# Power_Supply_Section.net
KiCad netlist of a schematic drawn in Altium Designer
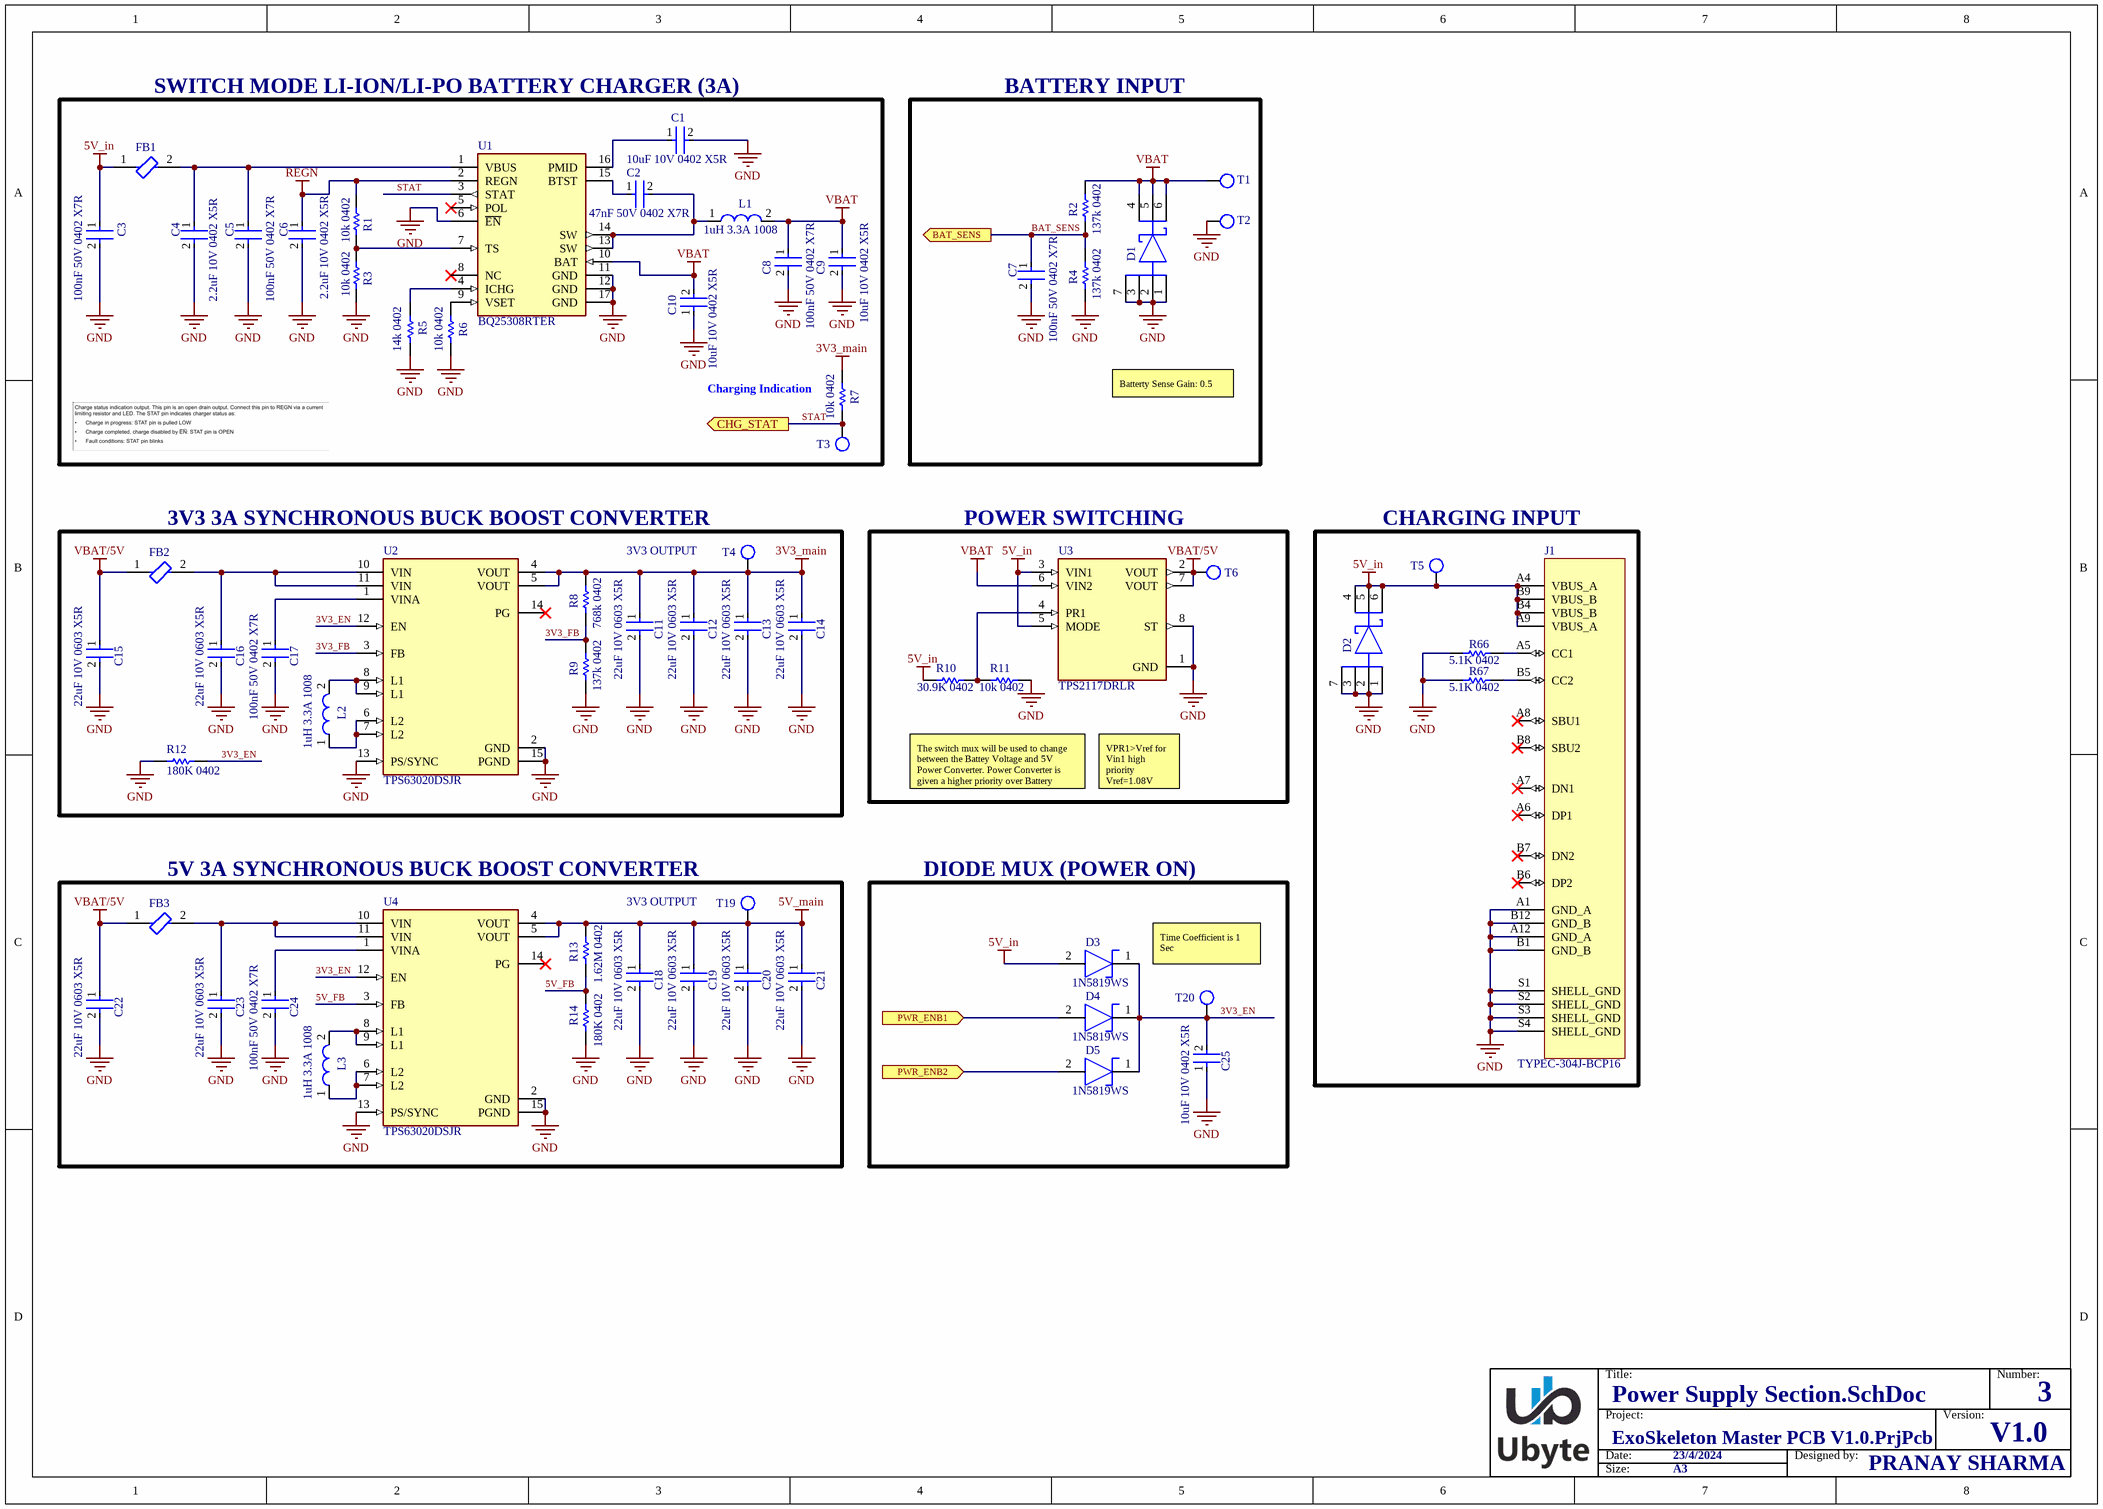
[diagram p0: Power Supply Section.SchDoc]

(export (version "E")
  (design (tool "Eeschema 10.0.6"))
  (components
    (comp (ref "C1")
      (value "10uF 10V 0402 X5R")
      (footprint "Res, Cap, Ind, LED, FB_Lib:0402 IPC CLASS C CAPACITOR")
      (libsource (lib "Capacitor_Lib") (part "10uF 10V 0402 X5R"))
    )
    (comp (ref "C2")
      (value "47nF 50V 0402 X7R")
      (footprint "Res, Cap, Ind, LED, FB_Lib:0402 IPC CLASS C CAPACITOR")
      (libsource (lib "Capacitor_Lib") (part "47nF 50V 0402 X7R"))
    )
    (comp (ref "C3")
      (value "100nF 50V 0402 X7R")
      (footprint "Res, Cap, Ind, LED, FB_Lib:0402 IPC CLASS C CAPACITOR")
      (libsource (lib "Capacitor_Lib") (part "100nF 50V 0402 X7R"))
    )
    (comp (ref "C4")
      (value "2.2uF 10V 0402 X5R")
      (footprint "Res, Cap, Ind, LED, FB_Lib:0402 IPC CLASS C CAPACITOR")
      (libsource (lib "Capacitor_Lib") (part "2.2uF 10V 0402 X5R"))
    )
    (comp (ref "C5")
      (value "100nF 50V 0402 X7R")
      (footprint "Res, Cap, Ind, LED, FB_Lib:0402 IPC CLASS C CAPACITOR")
      (libsource (lib "Capacitor_Lib") (part "100nF 50V 0402 X7R"))
    )
    (comp (ref "C6")
      (value "2.2uF 10V 0402 X5R")
      (footprint "Res, Cap, Ind, LED, FB_Lib:0402 IPC CLASS C CAPACITOR")
      (libsource (lib "Capacitor_Lib") (part "2.2uF 10V 0402 X5R"))
    )
    (comp (ref "C7")
      (value "100nF 50V 0402 X7R")
      (footprint "Res, Cap, Ind, LED, FB_Lib:0402 IPC CLASS C CAPACITOR")
      (libsource (lib "Capacitor_Lib") (part "100nF 50V 0402 X7R"))
    )
    (comp (ref "C8")
      (value "100nF 50V 0402 X7R")
      (footprint "Res, Cap, Ind, LED, FB_Lib:0402 IPC CLASS C CAPACITOR")
      (libsource (lib "Capacitor_Lib") (part "100nF 50V 0402 X7R"))
    )
    (comp (ref "C9")
      (value "10uF 10V 0402 X5R")
      (footprint "Res, Cap, Ind, LED, FB_Lib:0402 IPC CLASS C CAPACITOR")
      (libsource (lib "Capacitor_Lib") (part "10uF 10V 0402 X5R"))
    )
    (comp (ref "C10")
      (value "10uF 10V 0402 X5R")
      (footprint "Res, Cap, Ind, LED, FB_Lib:0402 IPC CLASS C CAPACITOR")
      (libsource (lib "Capacitor_Lib") (part "10uF 10V 0402 X5R"))
    )
    (comp (ref "C11")
      (value "22uF 10V 0603 X5R")
      (footprint "Res, Cap, Ind, LED, FB_Lib:0603 IPC CLASS C CAPACITOR")
      (libsource (lib "Capacitor_Lib") (part "22uF 10V 0603 X5R"))
    )
    (comp (ref "C12")
      (value "22uF 10V 0603 X5R")
      (footprint "Res, Cap, Ind, LED, FB_Lib:0603 IPC CLASS C CAPACITOR")
      (libsource (lib "Capacitor_Lib") (part "22uF 10V 0603 X5R"))
    )
    (comp (ref "C13")
      (value "22uF 10V 0603 X5R")
      (footprint "Res, Cap, Ind, LED, FB_Lib:0603 IPC CLASS C CAPACITOR")
      (libsource (lib "Capacitor_Lib") (part "22uF 10V 0603 X5R"))
    )
    (comp (ref "C14")
      (value "22uF 10V 0603 X5R")
      (footprint "Res, Cap, Ind, LED, FB_Lib:0603 IPC CLASS C CAPACITOR")
      (libsource (lib "Capacitor_Lib") (part "22uF 10V 0603 X5R"))
    )
    (comp (ref "C15")
      (value "22uF 10V 0603 X5R")
      (footprint "Res, Cap, Ind, LED, FB_Lib:0603 IPC CLASS C CAPACITOR")
      (libsource (lib "Capacitor_Lib") (part "22uF 10V 0603 X5R"))
    )
    (comp (ref "C16")
      (value "22uF 10V 0603 X5R")
      (footprint "Res, Cap, Ind, LED, FB_Lib:0603 IPC CLASS C CAPACITOR")
      (libsource (lib "Capacitor_Lib") (part "22uF 10V 0603 X5R"))
    )
    (comp (ref "C17")
      (value "100nF 50V 0402 X7R")
      (footprint "Res, Cap, Ind, LED, FB_Lib:0402 IPC CLASS C CAPACITOR")
      (libsource (lib "Capacitor_Lib") (part "100nF 50V 0402 X7R"))
    )
    (comp (ref "C18")
      (value "22uF 10V 0603 X5R")
      (footprint "Res, Cap, Ind, LED, FB_Lib:0603 IPC CLASS C CAPACITOR")
      (libsource (lib "Capacitor_Lib") (part "22uF 10V 0603 X5R"))
    )
    (comp (ref "C19")
      (value "22uF 10V 0603 X5R")
      (footprint "Res, Cap, Ind, LED, FB_Lib:0603 IPC CLASS C CAPACITOR")
      (libsource (lib "Capacitor_Lib") (part "22uF 10V 0603 X5R"))
    )
    (comp (ref "C20")
      (value "22uF 10V 0603 X5R")
      (footprint "Res, Cap, Ind, LED, FB_Lib:0603 IPC CLASS C CAPACITOR")
      (libsource (lib "Capacitor_Lib") (part "22uF 10V 0603 X5R"))
    )
    (comp (ref "C21")
      (value "22uF 10V 0603 X5R")
      (footprint "Res, Cap, Ind, LED, FB_Lib:0603 IPC CLASS C CAPACITOR")
      (libsource (lib "Capacitor_Lib") (part "22uF 10V 0603 X5R"))
    )
    (comp (ref "C22")
      (value "22uF 10V 0603 X5R")
      (footprint "Res, Cap, Ind, LED, FB_Lib:0603 IPC CLASS C CAPACITOR")
      (libsource (lib "Capacitor_Lib") (part "22uF 10V 0603 X5R"))
    )
    (comp (ref "C23")
      (value "22uF 10V 0603 X5R")
      (footprint "Res, Cap, Ind, LED, FB_Lib:0603 IPC CLASS C CAPACITOR")
      (libsource (lib "Capacitor_Lib") (part "22uF 10V 0603 X5R"))
    )
    (comp (ref "C24")
      (value "100nF 50V 0402 X7R")
      (footprint "Res, Cap, Ind, LED, FB_Lib:0402 IPC CLASS C CAPACITOR")
      (libsource (lib "Capacitor_Lib") (part "100nF 50V 0402 X7R"))
    )
    (comp (ref "C25")
      (value "10uF 10V 0402 X5R")
      (footprint "Res, Cap, Ind, LED, FB_Lib:0402 IPC CLASS C CAPACITOR")
      (libsource (lib "Capacitor_Lib") (part "10uF 10V 0402 X5R"))
    )
    (comp (ref "D1")
      (value "~")
      (footprint "Res, Cap, Ind, LED, FB_Lib:DRV0006A IPC-C")
      (libsource (lib "Diodes_Lib") (part "TVS0500DRVR"))
    )
    (comp (ref "D2")
      (value "~")
      (footprint "Res, Cap, Ind, LED, FB_Lib:DRV0006A IPC-C")
      (libsource (lib "Diodes_Lib") (part "TVS0500DRVR"))
    )
    (comp (ref "D3")
      (value "1N5819WS")
      (footprint "Res, Cap, Ind, LED, FB_Lib:SOD-323 IPC-C")
      (libsource (lib "Diodes_Lib") (part "1N5819WS"))
    )
    (comp (ref "D4")
      (value "1N5819WS")
      (footprint "Res, Cap, Ind, LED, FB_Lib:SOD-323 IPC-C")
      (libsource (lib "Diodes_Lib") (part "1N5819WS"))
    )
    (comp (ref "D5")
      (value "1N5819WS")
      (footprint "Res, Cap, Ind, LED, FB_Lib:SOD-323 IPC-C")
      (libsource (lib "Diodes_Lib") (part "1N5819WS"))
    )
    (comp (ref "FB1")
      (value "BLM21SP111SN1D")
      (footprint "Res, Cap, Ind, LED, FB_Lib:0603 IPC CLASS C FERRITE BEAD")
      (libsource (lib "Ferrite_Bead_Lib") (part "BLM21SP111SN1D"))
    )
    (comp (ref "FB2")
      (value "BLM21SP111SN1D")
      (footprint "Res, Cap, Ind, LED, FB_Lib:0603 IPC CLASS C FERRITE BEAD")
      (libsource (lib "Ferrite_Bead_Lib") (part "BLM21SP111SN1D"))
    )
    (comp (ref "FB3")
      (value "BLM21SP111SN1D")
      (footprint "Res, Cap, Ind, LED, FB_Lib:0603 IPC CLASS C FERRITE BEAD")
      (libsource (lib "Ferrite_Bead_Lib") (part "BLM21SP111SN1D"))
    )
    (comp (ref "J1")
      (value "TYPEC-304J-BCP16")
      (footprint "VALCON_CSP-USC16-TR")
      (libsource (lib "V1.0") (part "USB Type C"))
    )
    (comp (ref "L1")
      (value "1uH 3.3A 1008")
      (footprint "Res, Cap, Ind, LED, FB_Lib:1008 Inductor IPC-C")
      (libsource (lib "Inductor_Lib") (part "DFE252012F-1R0M=P2"))
    )
    (comp (ref "L2")
      (value "1uH 3.3A 1008")
      (footprint "Res, Cap, Ind, LED, FB_Lib:1008 Inductor IPC-C")
      (libsource (lib "Inductor_Lib") (part "DFE252012F-1R0M=P2"))
    )
    (comp (ref "L3")
      (value "1uH 3.3A 1008")
      (footprint "Res, Cap, Ind, LED, FB_Lib:1008 Inductor IPC-C")
      (libsource (lib "Inductor_Lib") (part "DFE252012F-1R0M=P2"))
    )
    (comp (ref "R1")
      (value "10k 0402")
      (footprint "Res, Cap, Ind, LED, FB_Lib:0402 IPC CLASS C RESISTOR")
      (libsource (lib "Resistor_Lib") (part "10k 1% 0402"))
    )
    (comp (ref "R2")
      (value "137k 0402")
      (footprint "Res, Cap, Ind, LED, FB_Lib:0402 IPC CLASS C RESISTOR")
      (libsource (lib "Resistor_Lib") (part "10k 1% 0402"))
    )
    (comp (ref "R3")
      (value "10k 0402")
      (footprint "Res, Cap, Ind, LED, FB_Lib:0402 IPC CLASS C RESISTOR")
      (libsource (lib "Resistor_Lib") (part "10k 1% 0402"))
    )
    (comp (ref "R4")
      (value "137k 0402")
      (footprint "Res, Cap, Ind, LED, FB_Lib:0402 IPC CLASS C RESISTOR")
      (libsource (lib "Resistor_Lib") (part "10k 1% 0402"))
    )
    (comp (ref "R5")
      (value "14k 0402")
      (footprint "Res, Cap, Ind, LED, FB_Lib:0402 IPC CLASS C RESISTOR")
      (libsource (lib "Resistor_Lib") (part "14k 1% 0402"))
    )
    (comp (ref "R6")
      (value "10k 0402")
      (footprint "Res, Cap, Ind, LED, FB_Lib:0402 IPC CLASS C RESISTOR")
      (libsource (lib "Resistor_Lib") (part "10k 1% 0402"))
    )
    (comp (ref "R7")
      (value "10k 0402")
      (footprint "Res, Cap, Ind, LED, FB_Lib:0402 IPC CLASS C RESISTOR")
      (libsource (lib "Resistor_Lib") (part "10k 1% 0402"))
    )
    (comp (ref "R8")
      (value "768k 0402")
      (footprint "Res, Cap, Ind, LED, FB_Lib:0402 IPC CLASS C RESISTOR")
      (libsource (lib "Resistor_Lib") (part "10k 1% 0402"))
    )
    (comp (ref "R9")
      (value "137k 0402")
      (footprint "Res, Cap, Ind, LED, FB_Lib:0402 IPC CLASS C RESISTOR")
      (libsource (lib "Resistor_Lib") (part "10k 1% 0402"))
    )
    (comp (ref "R10")
      (value "30.9K 0402")
      (footprint "Res, Cap, Ind, LED, FB_Lib:0402 IPC CLASS C RESISTOR")
      (libsource (lib "Resistor_Lib") (part "30.9K 1%  0402"))
    )
    (comp (ref "R11")
      (value "10k 0402")
      (footprint "Res, Cap, Ind, LED, FB_Lib:0402 IPC CLASS C RESISTOR")
      (libsource (lib "Resistor_Lib") (part "10k 1% 0402"))
    )
    (comp (ref "R12")
      (value "180K 0402")
      (footprint "Res, Cap, Ind, LED, FB_Lib:0402 IPC CLASS C RESISTOR")
      (libsource (lib "Resistor_Lib") (part "180K 1% 0402"))
    )
    (comp (ref "R13")
      (value "1.62M 0402")
      (footprint "Res, Cap, Ind, LED, FB_Lib:0402 IPC CLASS C RESISTOR")
      (libsource (lib "Resistor_Lib") (part "1.62M 1% 0402"))
    )
    (comp (ref "R14")
      (value "180K 0402")
      (footprint "Res, Cap, Ind, LED, FB_Lib:0402 IPC CLASS C RESISTOR")
      (libsource (lib "Resistor_Lib") (part "180K 1% 0402"))
    )
    (comp (ref "R66")
      (value "5.1K 0402")
      (footprint "Res, Cap, Ind, LED, FB_Lib:0402 IPC CLASS C RESISTOR")
      (libsource (lib "Resistor_Lib") (part "5.1K 1% 0402"))
    )
    (comp (ref "R67")
      (value "5.1K 0402")
      (footprint "Res, Cap, Ind, LED, FB_Lib:0402 IPC CLASS C RESISTOR")
      (libsource (lib "Resistor_Lib") (part "5.1K 1% 0402"))
    )
    (comp (ref "T1")
      (value "Test Point TH")
      (footprint "Miscellaneous_Lib:Test Point TH")
      (libsource (lib "Miscellaneous_Lib") (part "Test Point TH"))
    )
    (comp (ref "T2")
      (value "Test Point TH")
      (footprint "Miscellaneous_Lib:Test Point TH")
      (libsource (lib "Miscellaneous_Lib") (part "Test Point TH"))
    )
    (comp (ref "T3")
      (value "TP")
      (footprint "Miscellaneous_Lib:Testpoint1")
      (libsource (lib "Miscellaneous_Lib") (part "Testpoint1"))
    )
    (comp (ref "T4")
      (value "TP")
      (footprint "Miscellaneous_Lib:Testpoint1")
      (libsource (lib "Miscellaneous_Lib") (part "Testpoint1"))
    )
    (comp (ref "T5")
      (value "TP")
      (footprint "Miscellaneous_Lib:Testpoint1")
      (libsource (lib "Miscellaneous_Lib") (part "Testpoint1"))
    )
    (comp (ref "T6")
      (value "TP")
      (footprint "Miscellaneous_Lib:Testpoint1")
      (libsource (lib "Miscellaneous_Lib") (part "Testpoint1"))
    )
    (comp (ref "T19")
      (value "TP")
      (footprint "Miscellaneous_Lib:Testpoint1")
      (libsource (lib "Miscellaneous_Lib") (part "Testpoint1"))
    )
    (comp (ref "T20")
      (value "TP")
      (footprint "Miscellaneous_Lib:Testpoint1")
      (libsource (lib "Miscellaneous_Lib") (part "Testpoint1"))
    )
    (comp (ref "U1")
      (value "BQ25308RTER")
      (footprint "Integrated_Circuits_Lib:RTE0016C IPC-C")
      (libsource (lib "Integrated_Circuits_Lib") (part "BQ25308RTER"))
    )
    (comp (ref "U2")
      (value "TPS63020DSJR")
      (footprint "FP-DSJ0014A-MFG")
      (libsource (lib "Altium Content Vault") (part "ca84f4b88d1e031d86a58c77b9c066d"))
    )
    (comp (ref "U3")
      (value "TPS2117DRLR")
      (footprint "Integrated_Circuits_Lib:DRL0008A IPC-C")
      (libsource (lib "Integrated_Circuits_Lib") (part "TPS2117DRLR"))
    )
    (comp (ref "U4")
      (value "TPS63020DSJR")
      (footprint "FP-DSJ0014A-MFG")
      (libsource (lib "Altium Content Vault") (part "ca84f4b88d1e031d86a58c77b9c066d"))
    )
  )
  (nets
    (net (code "1") (name "/3V3_EN") (class "Default")
      (node (ref "C25") (pin "2") (pinfunction "2_2") (pintype "passive"))
      (node (ref "D3") (pin "1") (pinfunction "C_1") (pintype "passive"))
      (node (ref "D4") (pin "1") (pinfunction "C_1") (pintype "passive"))
      (node (ref "D5") (pin "1") (pinfunction "C_1") (pintype "passive"))
      (node (ref "R12") (pin "1") (pinfunction "1_1") (pintype "passive"))
      (node (ref "T20") (pin "0") (pinfunction "0_0") (pintype "passive"))
      (node (ref "U2") (pin "12") (pinfunction "EN_12") (pintype "input"))
      (node (ref "U4") (pin "12") (pinfunction "EN_12") (pintype "input"))
    )
    (net (code "2") (name "/3V3_FB") (class "Default")
      (node (ref "R8") (pin "2") (pinfunction "2_2") (pintype "passive"))
      (node (ref "R9") (pin "2") (pinfunction "2_2") (pintype "passive"))
      (node (ref "U2") (pin "3") (pinfunction "FB_3") (pintype "input"))
    )
    (net (code "3") (name "/5V_FB") (class "Default")
      (node (ref "R13") (pin "1") (pinfunction "1_1") (pintype "passive"))
      (node (ref "R14") (pin "2") (pinfunction "2_2") (pintype "passive"))
      (node (ref "U4") (pin "3") (pinfunction "FB_3") (pintype "input"))
    )
    (net (code "4") (name "/BAT_SENS") (class "Default")
      (node (ref "C7") (pin "1") (pinfunction "1_1") (pintype "passive"))
      (node (ref "R2") (pin "1") (pinfunction "1_1") (pintype "passive"))
      (node (ref "R4") (pin "2") (pinfunction "2_2") (pintype "passive"))
    )
    (net (code "5") (name "/PWR_ENB1") (class "Default")
      (node (ref "D4") (pin "2") (pinfunction "A_2") (pintype "passive"))
    )
    (net (code "6") (name "/PWR_ENB2") (class "Default")
      (node (ref "D5") (pin "2") (pinfunction "A_2") (pintype "passive"))
    )
    (net (code "7") (name "/STAT") (class "Default")
      (node (ref "R7") (pin "1") (pinfunction "1_1") (pintype "passive"))
      (node (ref "T3") (pin "0") (pinfunction "0_0") (pintype "passive"))
      (node (ref "U1") (pin "3") (pinfunction "STAT_3") (pintype "output"))
    )
    (net (code "8") (name "3V3_main") (class "Default")
      (node (ref "C11") (pin "1") (pinfunction "1_1") (pintype "passive"))
      (node (ref "C12") (pin "1") (pinfunction "1_1") (pintype "passive"))
      (node (ref "C13") (pin "1") (pinfunction "1_1") (pintype "passive"))
      (node (ref "C14") (pin "1") (pinfunction "1_1") (pintype "passive"))
      (node (ref "R7") (pin "2") (pinfunction "2_2") (pintype "passive"))
      (node (ref "R8") (pin "1") (pinfunction "1_1") (pintype "passive"))
      (node (ref "T4") (pin "0") (pinfunction "0_0") (pintype "passive"))
      (node (ref "U2") (pin "4") (pinfunction "VOUT_4") (pintype "power_in"))
      (node (ref "U2") (pin "5") (pinfunction "VOUT_5") (pintype "power_in"))
    )
    (net (code "9") (name "5V_in") (class "Default")
      (node (ref "C3") (pin "1") (pinfunction "1_1") (pintype "passive"))
      (node (ref "D2") (pin "4") (pinfunction "4_4") (pintype "passive"))
      (node (ref "D2") (pin "5") (pinfunction "5_5") (pintype "passive"))
      (node (ref "D2") (pin "6") (pinfunction "6_6") (pintype "passive"))
      (node (ref "D3") (pin "2") (pinfunction "A_2") (pintype "passive"))
      (node (ref "FB1") (pin "1") (pinfunction "1_1") (pintype "passive"))
      (node (ref "J1") (pin "A4") (pinfunction "VBUS_A_A4") (pintype "power_in"))
      (node (ref "J1") (pin "A9") (pinfunction "VBUS_A_A9") (pintype "power_in"))
      (node (ref "J1") (pin "B4") (pinfunction "VBUS_B_B4") (pintype "power_in"))
      (node (ref "J1") (pin "B9") (pinfunction "VBUS_B_B9") (pintype "power_in"))
      (node (ref "R10") (pin "2") (pinfunction "2_2") (pintype "passive"))
      (node (ref "T5") (pin "0") (pinfunction "0_0") (pintype "passive"))
      (node (ref "U3") (pin "3") (pinfunction "VIN1_3") (pintype "input"))
      (node (ref "U3") (pin "5") (pinfunction "MODE_5") (pintype "input"))
    )
    (net (code "10") (name "5V_main") (class "Default")
      (node (ref "C18") (pin "1") (pinfunction "1_1") (pintype "passive"))
      (node (ref "C19") (pin "1") (pinfunction "1_1") (pintype "passive"))
      (node (ref "C20") (pin "1") (pinfunction "1_1") (pintype "passive"))
      (node (ref "C21") (pin "1") (pinfunction "1_1") (pintype "passive"))
      (node (ref "R13") (pin "2") (pinfunction "2_2") (pintype "passive"))
      (node (ref "T19") (pin "0") (pinfunction "0_0") (pintype "passive"))
      (node (ref "U4") (pin "4") (pinfunction "VOUT_4") (pintype "power_in"))
      (node (ref "U4") (pin "5") (pinfunction "VOUT_5") (pintype "power_in"))
    )
    (net (code "11") (name "GND") (class "Default")
      (node (ref "C1") (pin "2") (pinfunction "2_2") (pintype "passive"))
      (node (ref "C10") (pin "1") (pinfunction "1_1") (pintype "passive"))
      (node (ref "C11") (pin "2") (pinfunction "2_2") (pintype "passive"))
      (node (ref "C12") (pin "2") (pinfunction "2_2") (pintype "passive"))
      (node (ref "C13") (pin "2") (pinfunction "2_2") (pintype "passive"))
      (node (ref "C14") (pin "2") (pinfunction "2_2") (pintype "passive"))
      (node (ref "C15") (pin "2") (pinfunction "2_2") (pintype "passive"))
      (node (ref "C16") (pin "2") (pinfunction "2_2") (pintype "passive"))
      (node (ref "C17") (pin "2") (pinfunction "2_2") (pintype "passive"))
      (node (ref "C18") (pin "2") (pinfunction "2_2") (pintype "passive"))
      (node (ref "C19") (pin "2") (pinfunction "2_2") (pintype "passive"))
      (node (ref "C20") (pin "2") (pinfunction "2_2") (pintype "passive"))
      (node (ref "C21") (pin "2") (pinfunction "2_2") (pintype "passive"))
      (node (ref "C22") (pin "2") (pinfunction "2_2") (pintype "passive"))
      (node (ref "C23") (pin "2") (pinfunction "2_2") (pintype "passive"))
      (node (ref "C24") (pin "2") (pinfunction "2_2") (pintype "passive"))
      (node (ref "C25") (pin "1") (pinfunction "1_1") (pintype "passive"))
      (node (ref "C3") (pin "2") (pinfunction "2_2") (pintype "passive"))
      (node (ref "C4") (pin "2") (pinfunction "2_2") (pintype "passive"))
      (node (ref "C5") (pin "2") (pinfunction "2_2") (pintype "passive"))
      (node (ref "C6") (pin "2") (pinfunction "2_2") (pintype "passive"))
      (node (ref "C7") (pin "2") (pinfunction "2_2") (pintype "passive"))
      (node (ref "C8") (pin "2") (pinfunction "2_2") (pintype "passive"))
      (node (ref "C9") (pin "2") (pinfunction "2_2") (pintype "passive"))
      (node (ref "D1") (pin "1") (pinfunction "C_1") (pintype "passive"))
      (node (ref "D1") (pin "2") (pinfunction "A_2") (pintype "passive"))
      (node (ref "D1") (pin "3") (pinfunction "3_3") (pintype "passive"))
      (node (ref "D1") (pin "7") (pinfunction "7_7") (pintype "passive"))
      (node (ref "D2") (pin "1") (pinfunction "C_1") (pintype "passive"))
      (node (ref "D2") (pin "2") (pinfunction "A_2") (pintype "passive"))
      (node (ref "D2") (pin "3") (pinfunction "3_3") (pintype "passive"))
      (node (ref "D2") (pin "7") (pinfunction "7_7") (pintype "passive"))
      (node (ref "J1") (pin "A1") (pinfunction "GND_A_A1") (pintype "power_in"))
      (node (ref "J1") (pin "A12") (pinfunction "GND_A_A12") (pintype "power_in"))
      (node (ref "J1") (pin "B1") (pinfunction "GND_B_B1") (pintype "power_in"))
      (node (ref "J1") (pin "B12") (pinfunction "GND_B_B12") (pintype "power_in"))
      (node (ref "J1") (pin "S1") (pinfunction "SHELL_GND_S1") (pintype "power_in"))
      (node (ref "J1") (pin "S2") (pinfunction "SHELL_GND_S2") (pintype "power_in"))
      (node (ref "J1") (pin "S3") (pinfunction "SHELL_GND_S3") (pintype "power_in"))
      (node (ref "J1") (pin "S4") (pinfunction "SHELL_GND_S4") (pintype "power_in"))
      (node (ref "R11") (pin "1") (pinfunction "1_1") (pintype "passive"))
      (node (ref "R12") (pin "2") (pinfunction "2_2") (pintype "passive"))
      (node (ref "R14") (pin "1") (pinfunction "1_1") (pintype "passive"))
      (node (ref "R3") (pin "1") (pinfunction "1_1") (pintype "passive"))
      (node (ref "R4") (pin "1") (pinfunction "1_1") (pintype "passive"))
      (node (ref "R5") (pin "1") (pinfunction "1_1") (pintype "passive"))
      (node (ref "R6") (pin "1") (pinfunction "1_1") (pintype "passive"))
      (node (ref "R66") (pin "1") (pinfunction "1_1") (pintype "passive"))
      (node (ref "R67") (pin "1") (pinfunction "1_1") (pintype "passive"))
      (node (ref "R9") (pin "1") (pinfunction "1_1") (pintype "passive"))
      (node (ref "T2") (pin "0") (pinfunction "0_0") (pintype "passive"))
      (node (ref "U1") (pin "11") (pinfunction "GND_11") (pintype "power_in"))
      (node (ref "U1") (pin "12") (pinfunction "GND_12") (pintype "power_in"))
      (node (ref "U1") (pin "17") (pinfunction "GND_17") (pintype "power_in"))
      (node (ref "U1") (pin "6") (pinfunction "~{EN}_6") (pintype "passive"))
      (node (ref "U2") (pin "13") (pinfunction "PS/SYNC_13") (pintype "input"))
      (node (ref "U2") (pin "15") (pinfunction "PGND_15") (pintype "power_in"))
      (node (ref "U2") (pin "2") (pinfunction "GND_2") (pintype "power_in"))
      (node (ref "U3") (pin "1") (pinfunction "GND_1") (pintype "power_in"))
      (node (ref "U3") (pin "8") (pinfunction "ST_8") (pintype "output"))
      (node (ref "U4") (pin "13") (pinfunction "PS/SYNC_13") (pintype "input"))
      (node (ref "U4") (pin "15") (pinfunction "PGND_15") (pintype "power_in"))
      (node (ref "U4") (pin "2") (pinfunction "GND_2") (pintype "power_in"))
    )
    (net (code "12") (name "Net-(C2-Pad2)") (class "Default")
      (node (ref "C2") (pin "2") (pinfunction "2_2") (pintype "passive"))
      (node (ref "L1") (pin "1") (pinfunction "1_1") (pintype "passive"))
      (node (ref "U1") (pin "13") (pinfunction "SW_13") (pintype "output"))
      (node (ref "U1") (pin "14") (pinfunction "SW_14") (pintype "output"))
    )
    (net (code "13") (name "Net-(C16-Pad1)") (class "Default")
      (node (ref "C16") (pin "1") (pinfunction "1_1") (pintype "passive"))
      (node (ref "FB2") (pin "2") (pinfunction "2_2") (pintype "passive"))
      (node (ref "U2") (pin "10") (pinfunction "VIN_10") (pintype "power_in"))
      (node (ref "U2") (pin "11") (pinfunction "VIN_11") (pintype "power_in"))
    )
    (net (code "14") (name "Net-(C23-Pad1)") (class "Default")
      (node (ref "C23") (pin "1") (pinfunction "1_1") (pintype "passive"))
      (node (ref "FB3") (pin "2") (pinfunction "2_2") (pintype "passive"))
      (node (ref "U4") (pin "10") (pinfunction "VIN_10") (pintype "power_in"))
      (node (ref "U4") (pin "11") (pinfunction "VIN_11") (pintype "power_in"))
    )
    (net (code "15") (name "Net-(J1-CC1)") (class "Default")
      (node (ref "J1") (pin "A5") (pinfunction "CC1_A5") (pintype "bidirectional"))
      (node (ref "R66") (pin "2") (pinfunction "2_2") (pintype "passive"))
    )
    (net (code "16") (name "Net-(J1-CC2)") (class "Default")
      (node (ref "J1") (pin "B5") (pinfunction "CC2_B5") (pintype "bidirectional"))
      (node (ref "R67") (pin "2") (pinfunction "2_2") (pintype "passive"))
    )
    (net (code "17") (name "Net-(L2-Pad1)") (class "Default")
      (node (ref "L2") (pin "1") (pinfunction "1_1") (pintype "passive"))
      (node (ref "U2") (pin "6") (pinfunction "L2_6") (pintype "input"))
      (node (ref "U2") (pin "7") (pinfunction "L2_7") (pintype "input"))
    )
    (net (code "18") (name "Net-(L2-Pad2)") (class "Default")
      (node (ref "L2") (pin "2") (pinfunction "2_2") (pintype "passive"))
      (node (ref "U2") (pin "8") (pinfunction "L1_8") (pintype "input"))
      (node (ref "U2") (pin "9") (pinfunction "L1_9") (pintype "input"))
    )
    (net (code "19") (name "Net-(L3-Pad1)") (class "Default")
      (node (ref "L3") (pin "1") (pinfunction "1_1") (pintype "passive"))
      (node (ref "U4") (pin "6") (pinfunction "L2_6") (pintype "input"))
      (node (ref "U4") (pin "7") (pinfunction "L2_7") (pintype "input"))
    )
    (net (code "20") (name "Net-(L3-Pad2)") (class "Default")
      (node (ref "L3") (pin "2") (pinfunction "2_2") (pintype "passive"))
      (node (ref "U4") (pin "8") (pinfunction "L1_8") (pintype "input"))
      (node (ref "U4") (pin "9") (pinfunction "L1_9") (pintype "input"))
    )
    (net (code "21") (name "Net-(U1-BTST)") (class "Default")
      (node (ref "C2") (pin "1") (pinfunction "1_1") (pintype "passive"))
      (node (ref "U1") (pin "15") (pinfunction "BTST_15") (pintype "power_in"))
    )
    (net (code "22") (name "Net-(U1-ICHG)") (class "Default")
      (node (ref "R5") (pin "2") (pinfunction "2_2") (pintype "passive"))
      (node (ref "U1") (pin "4") (pinfunction "ICHG_4") (pintype "input"))
    )
    (net (code "23") (name "Net-(U1-PMID)") (class "Default")
      (node (ref "C1") (pin "1") (pinfunction "1_1") (pintype "passive"))
      (node (ref "U1") (pin "16") (pinfunction "PMID_16") (pintype "power_in"))
    )
    (net (code "24") (name "Net-(U1-TS)") (class "Default")
      (node (ref "R1") (pin "1") (pinfunction "1_1") (pintype "passive"))
      (node (ref "R3") (pin "2") (pinfunction "2_2") (pintype "passive"))
      (node (ref "U1") (pin "7") (pinfunction "TS_7") (pintype "input"))
    )
    (net (code "25") (name "Net-(U1-VBUS)") (class "Default")
      (node (ref "C4") (pin "1") (pinfunction "1_1") (pintype "passive"))
      (node (ref "C5") (pin "1") (pinfunction "1_1") (pintype "passive"))
      (node (ref "FB1") (pin "2") (pinfunction "2_2") (pintype "passive"))
      (node (ref "U1") (pin "1") (pinfunction "VBUS_1") (pintype "power_in"))
    )
    (net (code "26") (name "Net-(U1-VSET)") (class "Default")
      (node (ref "R6") (pin "2") (pinfunction "2_2") (pintype "passive"))
      (node (ref "U1") (pin "9") (pinfunction "VSET_9") (pintype "input"))
    )
    (net (code "27") (name "Net-(U2-VINA)") (class "Default")
      (node (ref "C17") (pin "1") (pinfunction "1_1") (pintype "passive"))
      (node (ref "U2") (pin "1") (pinfunction "VINA_1") (pintype "power_in"))
    )
    (net (code "28") (name "Net-(U3-PR1)") (class "Default")
      (node (ref "R10") (pin "1") (pinfunction "1_1") (pintype "passive"))
      (node (ref "R11") (pin "2") (pinfunction "2_2") (pintype "passive"))
      (node (ref "U3") (pin "4") (pinfunction "PR1_4") (pintype "input"))
    )
    (net (code "29") (name "Net-(U4-VINA)") (class "Default")
      (node (ref "C24") (pin "1") (pinfunction "1_1") (pintype "passive"))
      (node (ref "U4") (pin "1") (pinfunction "VINA_1") (pintype "power_in"))
    )
    (net (code "30") (name "REGN") (class "Default")
      (node (ref "C6") (pin "1") (pinfunction "1_1") (pintype "passive"))
      (node (ref "R1") (pin "2") (pinfunction "2_2") (pintype "passive"))
      (node (ref "U1") (pin "2") (pinfunction "REGN_2") (pintype "power_in"))
    )
    (net (code "31") (name "VBAT") (class "Default")
      (node (ref "C10") (pin "2") (pinfunction "2_2") (pintype "passive"))
      (node (ref "C8") (pin "1") (pinfunction "1_1") (pintype "passive"))
      (node (ref "C9") (pin "1") (pinfunction "1_1") (pintype "passive"))
      (node (ref "D1") (pin "4") (pinfunction "4_4") (pintype "passive"))
      (node (ref "D1") (pin "5") (pinfunction "5_5") (pintype "passive"))
      (node (ref "D1") (pin "6") (pinfunction "6_6") (pintype "passive"))
      (node (ref "L1") (pin "2") (pinfunction "2_2") (pintype "passive"))
      (node (ref "R2") (pin "2") (pinfunction "2_2") (pintype "passive"))
      (node (ref "T1") (pin "0") (pinfunction "0_0") (pintype "passive"))
      (node (ref "U1") (pin "10") (pinfunction "BAT_10") (pintype "input"))
      (node (ref "U3") (pin "6") (pinfunction "VIN2_6") (pintype "input"))
    )
    (net (code "32") (name "VBAT{slash}5V") (class "Default")
      (node (ref "C15") (pin "1") (pinfunction "1_1") (pintype "passive"))
      (node (ref "C22") (pin "1") (pinfunction "1_1") (pintype "passive"))
      (node (ref "FB2") (pin "1") (pinfunction "1_1") (pintype "passive"))
      (node (ref "FB3") (pin "1") (pinfunction "1_1") (pintype "passive"))
      (node (ref "T6") (pin "0") (pinfunction "0_0") (pintype "passive"))
      (node (ref "U3") (pin "2") (pinfunction "VOUT_2") (pintype "output"))
      (node (ref "U3") (pin "7") (pinfunction "VOUT_7") (pintype "output"))
    )
    (net (code "33") (name "unconnected-(J1-DN1-PadA7)") (class "Default")
      (node (ref "J1") (pin "A7") (pinfunction "DN1_A7") (pintype "bidirectional+no_connect"))
    )
    (net (code "34") (name "unconnected-(J1-DN2-PadB7)") (class "Default")
      (node (ref "J1") (pin "B7") (pinfunction "DN2_B7") (pintype "bidirectional+no_connect"))
    )
    (net (code "35") (name "unconnected-(J1-DP1-PadA6)") (class "Default")
      (node (ref "J1") (pin "A6") (pinfunction "DP1_A6") (pintype "bidirectional+no_connect"))
    )
    (net (code "36") (name "unconnected-(J1-DP2-PadB6)") (class "Default")
      (node (ref "J1") (pin "B6") (pinfunction "DP2_B6") (pintype "bidirectional+no_connect"))
    )
    (net (code "37") (name "unconnected-(J1-SBU1-PadA8)") (class "Default")
      (node (ref "J1") (pin "A8") (pinfunction "SBU1_A8") (pintype "bidirectional+no_connect"))
    )
    (net (code "38") (name "unconnected-(J1-SBU2-PadB8)") (class "Default")
      (node (ref "J1") (pin "B8") (pinfunction "SBU2_B8") (pintype "bidirectional+no_connect"))
    )
    (net (code "39") (name "unconnected-(U1-NC-Pad8)") (class "Default")
      (node (ref "U1") (pin "8") (pinfunction "NC_8") (pintype "passive+no_connect"))
    )
    (net (code "40") (name "unconnected-(U1-POL-Pad5)") (class "Default")
      (node (ref "U1") (pin "5") (pinfunction "POL_5") (pintype "input+no_connect"))
    )
    (net (code "41") (name "unconnected-(U2-PG-Pad14)") (class "Default")
      (node (ref "U2") (pin "14") (pinfunction "PG_14") (pintype "open_collector+no_connect"))
    )
    (net (code "42") (name "unconnected-(U4-PG-Pad14)") (class "Default")
      (node (ref "U4") (pin "14") (pinfunction "PG_14") (pintype "open_collector+no_connect"))
    )
  )
)
